# fs7_redraw.net
KiCad netlist of a schematic drawn in EAGLE
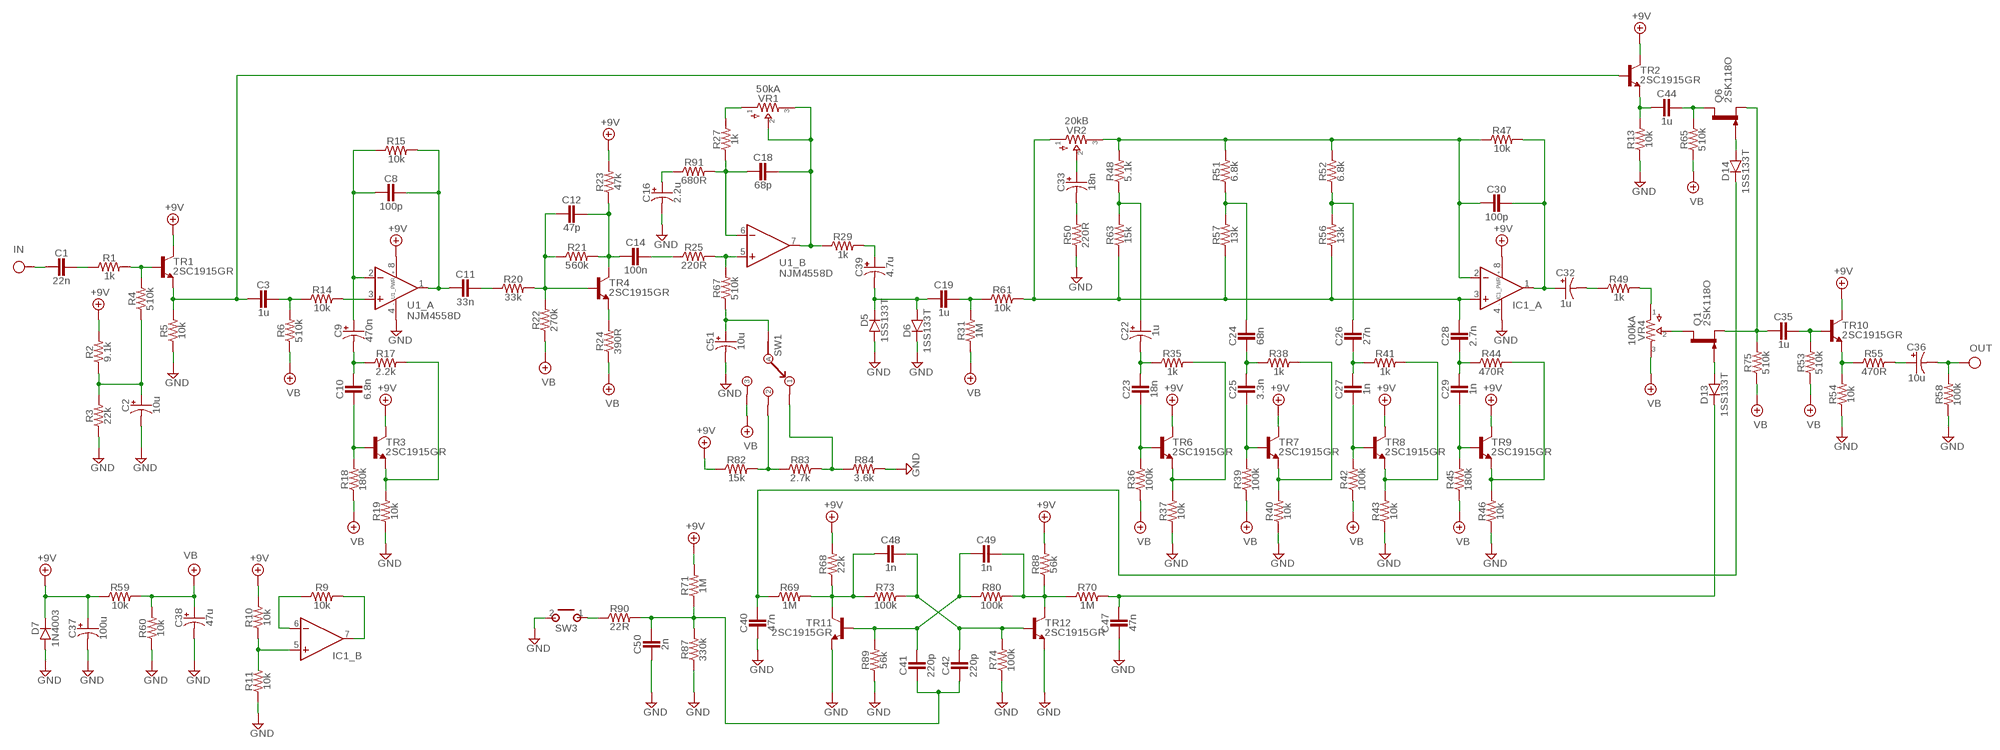
[diagram p0: schematic, sheet 1]

(export (version "E")
  (design (tool "Eeschema 10.0.6"))
  (components
    (comp (ref "C1")
      (value "22n")
      (footprint "eagle-import:BOX_SMALL")
      (libsource (lib "eagle-import") (part "CER/FILMBOX.1"))
    )
    (comp (ref "C2")
      (value "10u")
      (footprint "eagle-import:040_020")
      (libsource (lib "eagle-import") (part "0400"))
    )
    (comp (ref "C3")
      (value "1u")
      (footprint "eagle-import:BOX_SMALL")
      (libsource (lib "eagle-import") (part "CER/FILMBOX.1"))
    )
    (comp (ref "C8")
      (value "100p")
      (footprint "eagle-import:BOX_SMALL")
      (libsource (lib "eagle-import") (part "CER/FILMBOX.1"))
    )
    (comp (ref "C9")
      (value "470n")
      (footprint "eagle-import:040_020")
      (libsource (lib "eagle-import") (part "0400"))
    )
    (comp (ref "C10")
      (value "6.8n")
      (footprint "eagle-import:BOX_SMALL")
      (libsource (lib "eagle-import") (part "CER/FILMBOX.1"))
    )
    (comp (ref "C11")
      (value "33n")
      (footprint "eagle-import:BOX_SMALL")
      (libsource (lib "eagle-import") (part "CER/FILMBOX.1"))
    )
    (comp (ref "C12")
      (value "47p")
      (footprint "eagle-import:BOX_SMALL")
      (libsource (lib "eagle-import") (part "CER/FILMBOX.1"))
    )
    (comp (ref "C14")
      (value "100n")
      (footprint "eagle-import:BOX_SMALL")
      (libsource (lib "eagle-import") (part "CER/FILMBOX.1"))
    )
    (comp (ref "C16")
      (value "2.2u")
      (footprint "eagle-import:040_020")
      (libsource (lib "eagle-import") (part "0400"))
    )
    (comp (ref "C18")
      (value "68p")
      (footprint "eagle-import:BOX_SMALL")
      (libsource (lib "eagle-import") (part "CER/FILMBOX.1"))
    )
    (comp (ref "C19")
      (value "1u")
      (footprint "eagle-import:BOX_SMALL")
      (libsource (lib "eagle-import") (part "CER/FILMBOX.1"))
    )
    (comp (ref "C22")
      (value "1u")
      (footprint "eagle-import:040_020")
      (libsource (lib "eagle-import") (part "0400"))
    )
    (comp (ref "C23")
      (value "18n")
      (footprint "eagle-import:BOX_SMALL")
      (libsource (lib "eagle-import") (part "CER/FILMBOX.1"))
    )
    (comp (ref "C24")
      (value "68n")
      (footprint "eagle-import:BOX_SMALL")
      (libsource (lib "eagle-import") (part "CER/FILMBOX.1"))
    )
    (comp (ref "C25")
      (value "3.3n")
      (footprint "eagle-import:BOX_SMALL")
      (libsource (lib "eagle-import") (part "CER/FILMBOX.1"))
    )
    (comp (ref "C26")
      (value "27n")
      (footprint "eagle-import:BOX_SMALL")
      (libsource (lib "eagle-import") (part "CER/FILMBOX.1"))
    )
    (comp (ref "C27")
      (value "1n")
      (footprint "eagle-import:BOX_SMALL")
      (libsource (lib "eagle-import") (part "CER/FILMBOX.1"))
    )
    (comp (ref "C28")
      (value "2.7n")
      (footprint "eagle-import:BOX_SMALL")
      (libsource (lib "eagle-import") (part "CER/FILMBOX.1"))
    )
    (comp (ref "C29")
      (value "1n")
      (footprint "eagle-import:BOX_SMALL")
      (libsource (lib "eagle-import") (part "CER/FILMBOX.1"))
    )
    (comp (ref "C30")
      (value "100p")
      (footprint "eagle-import:BOX_SMALL")
      (libsource (lib "eagle-import") (part "CER/FILMBOX.1"))
    )
    (comp (ref "C32")
      (value "1u")
      (footprint "eagle-import:040_020")
      (libsource (lib "eagle-import") (part "0400"))
    )
    (comp (ref "C33")
      (value "18n")
      (footprint "eagle-import:040_020")
      (libsource (lib "eagle-import") (part "0400"))
    )
    (comp (ref "C35")
      (value "1u")
      (footprint "eagle-import:BOX_SMALL")
      (libsource (lib "eagle-import") (part "CER/FILMBOX.1"))
    )
    (comp (ref "C36")
      (value "10u")
      (footprint "eagle-import:040_020")
      (libsource (lib "eagle-import") (part "0400"))
    )
    (comp (ref "C37")
      (value "100u")
      (footprint "eagle-import:040_020")
      (libsource (lib "eagle-import") (part "0400"))
    )
    (comp (ref "C38")
      (value "47u")
      (footprint "eagle-import:040_020")
      (libsource (lib "eagle-import") (part "0400"))
    )
    (comp (ref "C39")
      (value "4.7u")
      (footprint "eagle-import:040_020")
      (libsource (lib "eagle-import") (part "0400"))
    )
    (comp (ref "C40")
      (value "47n")
      (footprint "eagle-import:BOX_SMALL")
      (libsource (lib "eagle-import") (part "CER/FILMBOX.1"))
    )
    (comp (ref "C41")
      (value "220p")
      (footprint "eagle-import:BOX_SMALL")
      (libsource (lib "eagle-import") (part "CER/FILMBOX.1"))
    )
    (comp (ref "C42")
      (value "220p")
      (footprint "eagle-import:BOX_SMALL")
      (libsource (lib "eagle-import") (part "CER/FILMBOX.1"))
    )
    (comp (ref "C44")
      (value "1u")
      (footprint "eagle-import:BOX_SMALL")
      (libsource (lib "eagle-import") (part "CER/FILMBOX.1"))
    )
    (comp (ref "C47")
      (value "47n")
      (footprint "eagle-import:BOX_SMALL")
      (libsource (lib "eagle-import") (part "CER/FILMBOX.1"))
    )
    (comp (ref "C48")
      (value "1n")
      (footprint "eagle-import:BOX_SMALL")
      (libsource (lib "eagle-import") (part "CER/FILMBOX.1"))
    )
    (comp (ref "C49")
      (value "1n")
      (footprint "eagle-import:BOX_SMALL")
      (libsource (lib "eagle-import") (part "CER/FILMBOX.1"))
    )
    (comp (ref "C50")
      (value "2n")
      (footprint "eagle-import:BOX_SMALL")
      (libsource (lib "eagle-import") (part "CER/FILMBOX.1"))
    )
    (comp (ref "C51")
      (value "10u")
      (footprint "eagle-import:040_020")
      (libsource (lib "eagle-import") (part "0400"))
    )
    (comp (ref "D5")
      (value "1SS133T")
      (footprint "eagle-import:DO41-2")
      (libsource (lib "eagle-import") (part "DO41.2"))
    )
    (comp (ref "D6")
      (value "1SS133T")
      (footprint "eagle-import:DO41-2")
      (libsource (lib "eagle-import") (part "DO41.2"))
    )
    (comp (ref "D7")
      (value "1N4003")
      (footprint "eagle-import:DO41-2")
      (libsource (lib "eagle-import") (part "DO41.2"))
    )
    (comp (ref "D13")
      (value "1SS133T")
      (footprint "eagle-import:DO41-2")
      (libsource (lib "eagle-import") (part "DO41.2"))
    )
    (comp (ref "D14")
      (value "1SS133T")
      (footprint "eagle-import:DO41-2")
      (libsource (lib "eagle-import") (part "DO41.2"))
    )
    (comp (ref "IC1")
      (value "DUALTH")
      (footprint "eagle-import:DIL0")
      (libsource (lib "eagle-import") (part "DUALTH"))
    )
    (comp (ref "Q1")
      (value "2SK118O")
      (footprint "eagle-import:TO92-")
      (libsource (lib "eagle-import") (part "2N5457"))
    )
    (comp (ref "Q6")
      (value "2SK118O")
      (footprint "eagle-import:TO92-")
      (libsource (lib "eagle-import") (part "2N5457"))
    )
    (comp (ref "R1")
      (value "1k")
      (footprint "eagle-import:R0207_3")
      (libsource (lib "eagle-import") (part "R_.3B"))
    )
    (comp (ref "R2")
      (value "9.1k")
      (footprint "eagle-import:R0207_3")
      (libsource (lib "eagle-import") (part "R_.3B"))
    )
    (comp (ref "R3")
      (value "22k")
      (footprint "eagle-import:R0207_3")
      (libsource (lib "eagle-import") (part "R_.3B"))
    )
    (comp (ref "R4")
      (value "510k")
      (footprint "eagle-import:R0207_3")
      (libsource (lib "eagle-import") (part "R_.3B"))
    )
    (comp (ref "R5")
      (value "10k")
      (footprint "eagle-import:R0207_3")
      (libsource (lib "eagle-import") (part "R_.3B"))
    )
    (comp (ref "R6")
      (value "510k")
      (footprint "eagle-import:R0207_3")
      (libsource (lib "eagle-import") (part "R_.3B"))
    )
    (comp (ref "R9")
      (value "10k")
      (footprint "eagle-import:R0207_3")
      (libsource (lib "eagle-import") (part "R_.3B"))
    )
    (comp (ref "R10")
      (value "10k")
      (footprint "eagle-import:R0207_3")
      (libsource (lib "eagle-import") (part "R_.3B"))
    )
    (comp (ref "R11")
      (value "10k")
      (footprint "eagle-import:R0207_3")
      (libsource (lib "eagle-import") (part "R_.3B"))
    )
    (comp (ref "R13")
      (value "10k")
      (footprint "eagle-import:R0207_3")
      (libsource (lib "eagle-import") (part "R_.3B"))
    )
    (comp (ref "R14")
      (value "10k")
      (footprint "eagle-import:R0207_3")
      (libsource (lib "eagle-import") (part "R_.3B"))
    )
    (comp (ref "R15")
      (value "10k")
      (footprint "eagle-import:R0207_3")
      (libsource (lib "eagle-import") (part "R_.3B"))
    )
    (comp (ref "R17")
      (value "2.2k")
      (footprint "eagle-import:R0207_3")
      (libsource (lib "eagle-import") (part "R_.3B"))
    )
    (comp (ref "R18")
      (value "180k")
      (footprint "eagle-import:R0207_3")
      (libsource (lib "eagle-import") (part "R_.3B"))
    )
    (comp (ref "R19")
      (value "10k")
      (footprint "eagle-import:R0207_3")
      (libsource (lib "eagle-import") (part "R_.3B"))
    )
    (comp (ref "R20")
      (value "33k")
      (footprint "eagle-import:R0207_3")
      (libsource (lib "eagle-import") (part "R_.3B"))
    )
    (comp (ref "R21")
      (value "560k")
      (footprint "eagle-import:R0207_3")
      (libsource (lib "eagle-import") (part "R_.3B"))
    )
    (comp (ref "R22")
      (value "270k")
      (footprint "eagle-import:R0207_3")
      (libsource (lib "eagle-import") (part "R_.3B"))
    )
    (comp (ref "R23")
      (value "47k")
      (footprint "eagle-import:R0207_3")
      (libsource (lib "eagle-import") (part "R_.3B"))
    )
    (comp (ref "R24")
      (value "390R")
      (footprint "eagle-import:R0207_3")
      (libsource (lib "eagle-import") (part "R_.3B"))
    )
    (comp (ref "R25")
      (value "220R")
      (footprint "eagle-import:R0207_3")
      (libsource (lib "eagle-import") (part "R_.3B"))
    )
    (comp (ref "R27")
      (value "1k")
      (footprint "eagle-import:R0207_3")
      (libsource (lib "eagle-import") (part "R_.3B"))
    )
    (comp (ref "R29")
      (value "1k")
      (footprint "eagle-import:R0207_3")
      (libsource (lib "eagle-import") (part "R_.3B"))
    )
    (comp (ref "R31")
      (value "1M")
      (footprint "eagle-import:R0207_3")
      (libsource (lib "eagle-import") (part "R_.3B"))
    )
    (comp (ref "R35")
      (value "1k")
      (footprint "eagle-import:R0207_3")
      (libsource (lib "eagle-import") (part "R_.3B"))
    )
    (comp (ref "R36")
      (value "100k")
      (footprint "eagle-import:R0207_3")
      (libsource (lib "eagle-import") (part "R_.3B"))
    )
    (comp (ref "R37")
      (value "10k")
      (footprint "eagle-import:R0207_3")
      (libsource (lib "eagle-import") (part "R_.3B"))
    )
    (comp (ref "R38")
      (value "1k")
      (footprint "eagle-import:R0207_3")
      (libsource (lib "eagle-import") (part "R_.3B"))
    )
    (comp (ref "R39")
      (value "100k")
      (footprint "eagle-import:R0207_3")
      (libsource (lib "eagle-import") (part "R_.3B"))
    )
    (comp (ref "R40")
      (value "10k")
      (footprint "eagle-import:R0207_3")
      (libsource (lib "eagle-import") (part "R_.3B"))
    )
    (comp (ref "R41")
      (value "1k")
      (footprint "eagle-import:R0207_3")
      (libsource (lib "eagle-import") (part "R_.3B"))
    )
    (comp (ref "R42")
      (value "100k")
      (footprint "eagle-import:R0207_3")
      (libsource (lib "eagle-import") (part "R_.3B"))
    )
    (comp (ref "R43")
      (value "10k")
      (footprint "eagle-import:R0207_3")
      (libsource (lib "eagle-import") (part "R_.3B"))
    )
    (comp (ref "R44")
      (value "470R")
      (footprint "eagle-import:R0207_3")
      (libsource (lib "eagle-import") (part "R_.3B"))
    )
    (comp (ref "R45")
      (value "180k")
      (footprint "eagle-import:R0207_3")
      (libsource (lib "eagle-import") (part "R_.3B"))
    )
    (comp (ref "R46")
      (value "10k")
      (footprint "eagle-import:R0207_3")
      (libsource (lib "eagle-import") (part "R_.3B"))
    )
    (comp (ref "R47")
      (value "10k")
      (footprint "eagle-import:R0207_3")
      (libsource (lib "eagle-import") (part "R_.3B"))
    )
    (comp (ref "R48")
      (value "5.1k")
      (footprint "eagle-import:R0207_3")
      (libsource (lib "eagle-import") (part "R_.3B"))
    )
    (comp (ref "R49")
      (value "1k")
      (footprint "eagle-import:R0207_3")
      (libsource (lib "eagle-import") (part "R_.3B"))
    )
    (comp (ref "R50")
      (value "220R")
      (footprint "eagle-import:R0207_3")
      (libsource (lib "eagle-import") (part "R_.3B"))
    )
    (comp (ref "R51")
      (value "6.8k")
      (footprint "eagle-import:R0207_3")
      (libsource (lib "eagle-import") (part "R_.3B"))
    )
    (comp (ref "R52")
      (value "6.8k")
      (footprint "eagle-import:R0207_3")
      (libsource (lib "eagle-import") (part "R_.3B"))
    )
    (comp (ref "R53")
      (value "510k")
      (footprint "eagle-import:R0207_3")
      (libsource (lib "eagle-import") (part "R_.3B"))
    )
    (comp (ref "R54")
      (value "10k")
      (footprint "eagle-import:R0207_3")
      (libsource (lib "eagle-import") (part "R_.3B"))
    )
    (comp (ref "R55")
      (value "470R")
      (footprint "eagle-import:R0207_3")
      (libsource (lib "eagle-import") (part "R_.3B"))
    )
    (comp (ref "R56")
      (value "13k")
      (footprint "eagle-import:R0207_3")
      (libsource (lib "eagle-import") (part "R_.3B"))
    )
    (comp (ref "R57")
      (value "13k")
      (footprint "eagle-import:R0207_3")
      (libsource (lib "eagle-import") (part "R_.3B"))
    )
    (comp (ref "R58")
      (value "100k")
      (footprint "eagle-import:R0207_3")
      (libsource (lib "eagle-import") (part "R_.3B"))
    )
    (comp (ref "R59")
      (value "10k")
      (footprint "eagle-import:R0207_3")
      (libsource (lib "eagle-import") (part "R_.3B"))
    )
    (comp (ref "R60")
      (value "10k")
      (footprint "eagle-import:R0207_3")
      (libsource (lib "eagle-import") (part "R_.3B"))
    )
    (comp (ref "R61")
      (value "10k")
      (footprint "eagle-import:R0207_3")
      (libsource (lib "eagle-import") (part "R_.3B"))
    )
    (comp (ref "R63")
      (value "15k")
      (footprint "eagle-import:R0207_3")
      (libsource (lib "eagle-import") (part "R_.3B"))
    )
    (comp (ref "R65")
      (value "510k")
      (footprint "eagle-import:R0207_3")
      (libsource (lib "eagle-import") (part "R_.3B"))
    )
    (comp (ref "R67")
      (value "510k")
      (footprint "eagle-import:R0207_3")
      (libsource (lib "eagle-import") (part "R_.3B"))
    )
    (comp (ref "R68")
      (value "22k")
      (footprint "eagle-import:R0207_3")
      (libsource (lib "eagle-import") (part "R_.3B"))
    )
    (comp (ref "R69")
      (value "1M")
      (footprint "eagle-import:R0207_3")
      (libsource (lib "eagle-import") (part "R_.3B"))
    )
    (comp (ref "R70")
      (value "1M")
      (footprint "eagle-import:R0207_3")
      (libsource (lib "eagle-import") (part "R_.3B"))
    )
    (comp (ref "R71")
      (value "1M")
      (footprint "eagle-import:R0207_3")
      (libsource (lib "eagle-import") (part "R_.3B"))
    )
    (comp (ref "R73")
      (value "100k")
      (footprint "eagle-import:R0207_3")
      (libsource (lib "eagle-import") (part "R_.3B"))
    )
    (comp (ref "R74")
      (value "100k")
      (footprint "eagle-import:R0207_3")
      (libsource (lib "eagle-import") (part "R_.3B"))
    )
    (comp (ref "R75")
      (value "510k")
      (footprint "eagle-import:R0207_3")
      (libsource (lib "eagle-import") (part "R_.3B"))
    )
    (comp (ref "R80")
      (value "100k")
      (footprint "eagle-import:R0207_3")
      (libsource (lib "eagle-import") (part "R_.3B"))
    )
    (comp (ref "R82")
      (value "15k")
      (footprint "eagle-import:R0207_3")
      (libsource (lib "eagle-import") (part "R_.3B"))
    )
    (comp (ref "R83")
      (value "2.7k")
      (footprint "eagle-import:R0207_3")
      (libsource (lib "eagle-import") (part "R_.3B"))
    )
    (comp (ref "R84")
      (value "3.6k")
      (footprint "eagle-import:R0207_3")
      (libsource (lib "eagle-import") (part "R_.3B"))
    )
    (comp (ref "R87")
      (value "330k")
      (footprint "eagle-import:R0207_3")
      (libsource (lib "eagle-import") (part "R_.3B"))
    )
    (comp (ref "R88")
      (value "56k")
      (footprint "eagle-import:R0207_3")
      (libsource (lib "eagle-import") (part "R_.3B"))
    )
    (comp (ref "R89")
      (value "56k")
      (footprint "eagle-import:R0207_3")
      (libsource (lib "eagle-import") (part "R_.3B"))
    )
    (comp (ref "R90")
      (value "22R")
      (footprint "eagle-import:R0207_3")
      (libsource (lib "eagle-import") (part "R_.3B"))
    )
    (comp (ref "R91")
      (value "680R")
      (footprint "eagle-import:R0207_3")
      (libsource (lib "eagle-import") (part "R_.3B"))
    )
    (comp (ref "SW1")
      (value "1P3T")
      (footprint "eagle-import:1P3T")
      (libsource (lib "eagle-import") (part "1P3T"))
    )
    (comp (ref "SW3")
      (value "MOMENTARY")
      (footprint "eagle-import:SPST")
      (libsource (lib "eagle-import") (part "MOMENTARY"))
    )
    (comp (ref "TR1")
      (value "2SC1915GR")
      (footprint "eagle-import:TO92-")
      (libsource (lib "eagle-import") (part "2SC828A"))
    )
    (comp (ref "TR2")
      (value "2SC1915GR")
      (footprint "eagle-import:TO92-")
      (libsource (lib "eagle-import") (part "2SC828A"))
    )
    (comp (ref "TR3")
      (value "2SC1915GR")
      (footprint "eagle-import:TO92-")
      (libsource (lib "eagle-import") (part "2SC828A"))
    )
    (comp (ref "TR4")
      (value "2SC1915GR")
      (footprint "eagle-import:TO92-")
      (libsource (lib "eagle-import") (part "2SC828A"))
    )
    (comp (ref "TR6")
      (value "2SC1915GR")
      (footprint "eagle-import:TO92-")
      (libsource (lib "eagle-import") (part "2SC828A"))
    )
    (comp (ref "TR7")
      (value "2SC1915GR")
      (footprint "eagle-import:TO92-")
      (libsource (lib "eagle-import") (part "2SC828A"))
    )
    (comp (ref "TR8")
      (value "2SC1915GR")
      (footprint "eagle-import:TO92-")
      (libsource (lib "eagle-import") (part "2SC828A"))
    )
    (comp (ref "TR9")
      (value "2SC1915GR")
      (footprint "eagle-import:TO92-")
      (libsource (lib "eagle-import") (part "2SC828A"))
    )
    (comp (ref "TR10")
      (value "2SC1915GR")
      (footprint "eagle-import:TO92-")
      (libsource (lib "eagle-import") (part "2SC828A"))
    )
    (comp (ref "TR11")
      (value "2SC1915GR")
      (footprint "eagle-import:TO92-")
      (libsource (lib "eagle-import") (part "2SC828A"))
    )
    (comp (ref "TR12")
      (value "2SC1915GR")
      (footprint "eagle-import:TO92-")
      (libsource (lib "eagle-import") (part "2SC828A"))
    )
    (comp (ref "U1")
      (value "NJM4558D")
      (footprint "eagle-import:DIL0")
      (libsource (lib "eagle-import") (part "DUALTH"))
    )
    (comp (ref "VR1")
      (value "50kA")
      (footprint "eagle-import:16MM")
      (libsource (lib "eagle-import") (part "POTS16MM"))
    )
    (comp (ref "VR2")
      (value "20kB")
      (footprint "eagle-import:16MM")
      (libsource (lib "eagle-import") (part "POTS16MM"))
    )
    (comp (ref "VR4")
      (value "100kA")
      (footprint "eagle-import:16MM")
      (libsource (lib "eagle-import") (part "POTS16MM"))
    )
  )
  (nets
    (net (code "1") (name "+9V") (class "Default")
      (node (ref "C37") (pin "+") (pinfunction "+_+") (pintype "passive"))
      (node (ref "D7") (pin "C") (pinfunction "C_C") (pintype "passive"))
      (node (ref "IC1") (pin "8") (pinfunction "V+_8") (pintype "power_in"))
      (node (ref "R10") (pin "2") (pinfunction "2_2") (pintype "passive"))
      (node (ref "R2") (pin "2") (pinfunction "2_2") (pintype "passive"))
      (node (ref "R23") (pin "2") (pinfunction "2_2") (pintype "passive"))
      (node (ref "R59") (pin "1") (pinfunction "1_1") (pintype "passive"))
      (node (ref "R68") (pin "2") (pinfunction "2_2") (pintype "passive"))
      (node (ref "R71") (pin "2") (pinfunction "2_2") (pintype "passive"))
      (node (ref "R82") (pin "1") (pinfunction "1_1") (pintype "passive"))
      (node (ref "R88") (pin "2") (pinfunction "2_2") (pintype "passive"))
      (node (ref "TR1") (pin "2") (pinfunction "C_2") (pintype "passive"))
      (node (ref "TR10") (pin "2") (pinfunction "C_2") (pintype "passive"))
      (node (ref "TR2") (pin "2") (pinfunction "C_2") (pintype "passive"))
      (node (ref "TR3") (pin "2") (pinfunction "C_2") (pintype "passive"))
      (node (ref "TR6") (pin "2") (pinfunction "C_2") (pintype "passive"))
      (node (ref "TR7") (pin "2") (pinfunction "C_2") (pintype "passive"))
      (node (ref "TR8") (pin "2") (pinfunction "C_2") (pintype "passive"))
      (node (ref "TR9") (pin "2") (pinfunction "C_2") (pintype "passive"))
      (node (ref "U1") (pin "8") (pinfunction "V+_8") (pintype "power_in"))
    )
    (net (code "2") (name "GND") (class "Default")
      (node (ref "C16") (pin "-") (pinfunction "-_-") (pintype "passive"))
      (node (ref "C2") (pin "-") (pinfunction "-_-") (pintype "passive"))
      (node (ref "C37") (pin "-") (pinfunction "-_-") (pintype "passive"))
      (node (ref "C38") (pin "-") (pinfunction "-_-") (pintype "passive"))
      (node (ref "C40") (pin "2") (pinfunction "2_2") (pintype "passive"))
      (node (ref "C47") (pin "2") (pinfunction "2_2") (pintype "passive"))
      (node (ref "C50") (pin "2") (pinfunction "2_2") (pintype "passive"))
      (node (ref "C51") (pin "-") (pinfunction "-_-") (pintype "passive"))
      (node (ref "D5") (pin "A") (pinfunction "A_A") (pintype "passive"))
      (node (ref "D6") (pin "C") (pinfunction "C_C") (pintype "passive"))
      (node (ref "D7") (pin "A") (pinfunction "A_A") (pintype "passive"))
      (node (ref "IC1") (pin "4") (pinfunction "V-_4") (pintype "power_in"))
      (node (ref "R11") (pin "1") (pinfunction "1_1") (pintype "passive"))
      (node (ref "R13") (pin "1") (pinfunction "1_1") (pintype "passive"))
      (node (ref "R19") (pin "1") (pinfunction "1_1") (pintype "passive"))
      (node (ref "R3") (pin "1") (pinfunction "1_1") (pintype "passive"))
      (node (ref "R37") (pin "1") (pinfunction "1_1") (pintype "passive"))
      (node (ref "R40") (pin "1") (pinfunction "1_1") (pintype "passive"))
      (node (ref "R43") (pin "1") (pinfunction "1_1") (pintype "passive"))
      (node (ref "R46") (pin "1") (pinfunction "1_1") (pintype "passive"))
      (node (ref "R5") (pin "1") (pinfunction "1_1") (pintype "passive"))
      (node (ref "R50") (pin "1") (pinfunction "1_1") (pintype "passive"))
      (node (ref "R54") (pin "1") (pinfunction "1_1") (pintype "passive"))
      (node (ref "R58") (pin "1") (pinfunction "1_1") (pintype "passive"))
      (node (ref "R60") (pin "1") (pinfunction "1_1") (pintype "passive"))
      (node (ref "R74") (pin "1") (pinfunction "1_1") (pintype "passive"))
      (node (ref "R84") (pin "2") (pinfunction "2_2") (pintype "passive"))
      (node (ref "R87") (pin "1") (pinfunction "1_1") (pintype "passive"))
      (node (ref "R89") (pin "1") (pinfunction "1_1") (pintype "passive"))
      (node (ref "SW3") (pin "2") (pinfunction "S_2") (pintype "passive"))
      (node (ref "TR11") (pin "3") (pinfunction "E_3") (pintype "passive"))
      (node (ref "TR12") (pin "3") (pinfunction "E_3") (pintype "passive"))
      (node (ref "U1") (pin "4") (pinfunction "V-_4") (pintype "power_in"))
    )
    (net (code "3") (name "IN") (class "Default")
      (node (ref "C1") (pin "2") (pinfunction "2_2") (pintype "passive"))
    )
    (net (code "4") (name "Net-(C1-Pad1)") (class "Default")
      (node (ref "C1") (pin "1") (pinfunction "1_1") (pintype "passive"))
      (node (ref "R1") (pin "1") (pinfunction "1_1") (pintype "passive"))
    )
    (net (code "5") (name "Net-(C2-Pad+)") (class "Default")
      (node (ref "C2") (pin "+") (pinfunction "+_+") (pintype "passive"))
      (node (ref "R2") (pin "1") (pinfunction "1_1") (pintype "passive"))
      (node (ref "R3") (pin "2") (pinfunction "2_2") (pintype "passive"))
      (node (ref "R4") (pin "1") (pinfunction "1_1") (pintype "passive"))
    )
    (net (code "6") (name "Net-(C3-Pad1)") (class "Default")
      (node (ref "C3") (pin "1") (pinfunction "1_1") (pintype "passive"))
      (node (ref "R14") (pin "1") (pinfunction "1_1") (pintype "passive"))
      (node (ref "R6") (pin "2") (pinfunction "2_2") (pintype "passive"))
    )
    (net (code "7") (name "Net-(C10-Pad1)") (class "Default")
      (node (ref "C10") (pin "1") (pinfunction "1_1") (pintype "passive"))
      (node (ref "C9") (pin "-") (pinfunction "-_-") (pintype "passive"))
      (node (ref "R17") (pin "1") (pinfunction "1_1") (pintype "passive"))
    )
    (net (code "8") (name "Net-(C11-Pad1)") (class "Default")
      (node (ref "C11") (pin "1") (pinfunction "1_1") (pintype "passive"))
      (node (ref "R20") (pin "1") (pinfunction "1_1") (pintype "passive"))
    )
    (net (code "9") (name "Net-(C14-Pad1)") (class "Default")
      (node (ref "C14") (pin "1") (pinfunction "1_1") (pintype "passive"))
      (node (ref "R25") (pin "1") (pinfunction "1_1") (pintype "passive"))
    )
    (net (code "10") (name "Net-(C16-Pad+)") (class "Default")
      (node (ref "C16") (pin "+") (pinfunction "+_+") (pintype "passive"))
      (node (ref "R91") (pin "1") (pinfunction "1_1") (pintype "passive"))
    )
    (net (code "11") (name "Net-(C19-Pad1)") (class "Default")
      (node (ref "C19") (pin "1") (pinfunction "1_1") (pintype "passive"))
      (node (ref "R31") (pin "2") (pinfunction "2_2") (pintype "passive"))
      (node (ref "R61") (pin "1") (pinfunction "1_1") (pintype "passive"))
    )
    (net (code "12") (name "Net-(C19-Pad2)") (class "Default")
      (node (ref "C19") (pin "2") (pinfunction "2_2") (pintype "passive"))
      (node (ref "C39") (pin "-") (pinfunction "-_-") (pintype "passive"))
      (node (ref "D5") (pin "C") (pinfunction "C_C") (pintype "passive"))
      (node (ref "D6") (pin "A") (pinfunction "A_A") (pintype "passive"))
    )
    (net (code "13") (name "Net-(C22-Pad+)") (class "Default")
      (node (ref "C22") (pin "+") (pinfunction "+_+") (pintype "passive"))
      (node (ref "R48") (pin "1") (pinfunction "1_1") (pintype "passive"))
      (node (ref "R63") (pin "2") (pinfunction "2_2") (pintype "passive"))
    )
    (net (code "14") (name "Net-(C22-Pad-)") (class "Default")
      (node (ref "C22") (pin "-") (pinfunction "-_-") (pintype "passive"))
      (node (ref "C23") (pin "1") (pinfunction "1_1") (pintype "passive"))
      (node (ref "R35") (pin "1") (pinfunction "1_1") (pintype "passive"))
    )
    (net (code "15") (name "Net-(C24-Pad1)") (class "Default")
      (node (ref "C24") (pin "1") (pinfunction "1_1") (pintype "passive"))
      (node (ref "R51") (pin "1") (pinfunction "1_1") (pintype "passive"))
      (node (ref "R57") (pin "2") (pinfunction "2_2") (pintype "passive"))
    )
    (net (code "16") (name "Net-(C24-Pad2)") (class "Default")
      (node (ref "C24") (pin "2") (pinfunction "2_2") (pintype "passive"))
      (node (ref "C25") (pin "1") (pinfunction "1_1") (pintype "passive"))
      (node (ref "R38") (pin "1") (pinfunction "1_1") (pintype "passive"))
    )
    (net (code "17") (name "Net-(C26-Pad1)") (class "Default")
      (node (ref "C26") (pin "1") (pinfunction "1_1") (pintype "passive"))
      (node (ref "R52") (pin "1") (pinfunction "1_1") (pintype "passive"))
      (node (ref "R56") (pin "2") (pinfunction "2_2") (pintype "passive"))
    )
    (net (code "18") (name "Net-(C26-Pad2)") (class "Default")
      (node (ref "C26") (pin "2") (pinfunction "2_2") (pintype "passive"))
      (node (ref "C27") (pin "1") (pinfunction "1_1") (pintype "passive"))
      (node (ref "R41") (pin "1") (pinfunction "1_1") (pintype "passive"))
    )
    (net (code "19") (name "Net-(C28-Pad2)") (class "Default")
      (node (ref "C28") (pin "2") (pinfunction "2_2") (pintype "passive"))
      (node (ref "C29") (pin "1") (pinfunction "1_1") (pintype "passive"))
      (node (ref "R44") (pin "1") (pinfunction "1_1") (pintype "passive"))
    )
    (net (code "20") (name "Net-(C32-Pad-)") (class "Default")
      (node (ref "C32") (pin "-") (pinfunction "-_-") (pintype "passive"))
      (node (ref "R49") (pin "1") (pinfunction "1_1") (pintype "passive"))
    )
    (net (code "21") (name "Net-(C33-Pad+)") (class "Default")
      (node (ref "C33") (pin "+") (pinfunction "+_+") (pintype "passive"))
      (node (ref "VR2") (pin "2") (pinfunction "2_2") (pintype "passive"))
    )
    (net (code "22") (name "Net-(C33-Pad-)") (class "Default")
      (node (ref "C33") (pin "-") (pinfunction "-_-") (pintype "passive"))
      (node (ref "R50") (pin "2") (pinfunction "2_2") (pintype "passive"))
    )
    (net (code "23") (name "Net-(C36-Pad+)") (class "Default")
      (node (ref "C36") (pin "+") (pinfunction "+_+") (pintype "passive"))
      (node (ref "R55") (pin "2") (pinfunction "2_2") (pintype "passive"))
    )
    (net (code "24") (name "Net-(C39-Pad+)") (class "Default")
      (node (ref "C39") (pin "+") (pinfunction "+_+") (pintype "passive"))
      (node (ref "R29") (pin "2") (pinfunction "2_2") (pintype "passive"))
    )
    (net (code "25") (name "Net-(C40-Pad1)") (class "Default")
      (node (ref "C40") (pin "1") (pinfunction "1_1") (pintype "passive"))
      (node (ref "D14") (pin "C") (pinfunction "C_C") (pintype "passive"))
      (node (ref "R69") (pin "1") (pinfunction "1_1") (pintype "passive"))
    )
    (net (code "26") (name "Net-(C41-Pad2)") (class "Default")
      (node (ref "C41") (pin "2") (pinfunction "2_2") (pintype "passive"))
      (node (ref "C42") (pin "2") (pinfunction "2_2") (pintype "passive"))
      (node (ref "C50") (pin "1") (pinfunction "1_1") (pintype "passive"))
      (node (ref "R71") (pin "1") (pinfunction "1_1") (pintype "passive"))
      (node (ref "R87") (pin "2") (pinfunction "2_2") (pintype "passive"))
      (node (ref "R90") (pin "2") (pinfunction "2_2") (pintype "passive"))
    )
    (net (code "27") (name "Net-(C47-Pad1)") (class "Default")
      (node (ref "C47") (pin "1") (pinfunction "1_1") (pintype "passive"))
      (node (ref "D13") (pin "C") (pinfunction "C_C") (pintype "passive"))
      (node (ref "R70") (pin "2") (pinfunction "2_2") (pintype "passive"))
    )
    (net (code "28") (name "Net-(IC1A-+IN)") (class "Default")
      (node (ref "C28") (pin "1") (pinfunction "1_1") (pintype "passive"))
      (node (ref "IC1") (pin "3") (pinfunction "+IN_3") (pintype "input"))
      (node (ref "R56") (pin "1") (pinfunction "1_1") (pintype "passive"))
      (node (ref "R57") (pin "1") (pinfunction "1_1") (pintype "passive"))
      (node (ref "R61") (pin "2") (pinfunction "2_2") (pintype "passive"))
      (node (ref "R63") (pin "1") (pinfunction "1_1") (pintype "passive"))
      (node (ref "VR2") (pin "1") (pinfunction "1_1") (pintype "passive"))
    )
    (net (code "29") (name "Net-(IC1A--IN)") (class "Default")
      (node (ref "C30") (pin "2") (pinfunction "2_2") (pintype "passive"))
      (node (ref "IC1") (pin "2") (pinfunction "-IN_2") (pintype "input"))
      (node (ref "R47") (pin "1") (pinfunction "1_1") (pintype "passive"))
      (node (ref "R48") (pin "2") (pinfunction "2_2") (pintype "passive"))
      (node (ref "R51") (pin "2") (pinfunction "2_2") (pintype "passive"))
      (node (ref "R52") (pin "2") (pinfunction "2_2") (pintype "passive"))
      (node (ref "VR2") (pin "3") (pinfunction "3_3") (pintype "passive"))
    )
    (net (code "30") (name "Net-(IC1A-OUT)") (class "Default")
      (node (ref "C30") (pin "1") (pinfunction "1_1") (pintype "passive"))
      (node (ref "C32") (pin "+") (pinfunction "+_+") (pintype "passive"))
      (node (ref "IC1") (pin "1") (pinfunction "OUT_1") (pintype "output"))
      (node (ref "R47") (pin "2") (pinfunction "2_2") (pintype "passive"))
    )
    (net (code "31") (name "Net-(IC1B-+IN)") (class "Default")
      (node (ref "IC1") (pin "5") (pinfunction "+IN_5") (pintype "input"))
      (node (ref "R10") (pin "1") (pinfunction "1_1") (pintype "passive"))
    )
    (net (code "32") (name "Net-(IC1B--IN)") (class "Default")
      (node (ref "IC1") (pin "6") (pinfunction "-IN_6") (pintype "input"))
      (node (ref "R9") (pin "1") (pinfunction "1_1") (pintype "passive"))
    )
    (net (code "33") (name "Net-(IC1B-OUT)") (class "Default")
      (node (ref "IC1") (pin "7") (pinfunction "OUT_7") (pintype "output"))
      (node (ref "R9") (pin "2") (pinfunction "2_2") (pintype "passive"))
    )
    (net (code "34") (name "Net-(Q1-D)") (class "Default")
      (node (ref "Q1") (pin "3") (pinfunction "D_3") (pintype "passive"))
      (node (ref "VR4") (pin "2") (pinfunction "2_2") (pintype "passive"))
    )
    (net (code "35") (name "Net-(Q1-G)") (class "Default")
      (node (ref "D13") (pin "A") (pinfunction "A_A") (pintype "passive"))
      (node (ref "Q1") (pin "1") (pinfunction "G_1") (pintype "passive"))
    )
    (net (code "36") (name "Net-(Q1-S)") (class "Default")
      (node (ref "C35") (pin "2") (pinfunction "2_2") (pintype "passive"))
      (node (ref "Q1") (pin "2") (pinfunction "S_2") (pintype "passive"))
      (node (ref "Q6") (pin "2") (pinfunction "S_2") (pintype "passive"))
      (node (ref "R75") (pin "2") (pinfunction "2_2") (pintype "passive"))
    )
    (net (code "37") (name "Net-(Q6-D)") (class "Default")
      (node (ref "C44") (pin "1") (pinfunction "1_1") (pintype "passive"))
      (node (ref "Q6") (pin "3") (pinfunction "D_3") (pintype "passive"))
      (node (ref "R65") (pin "2") (pinfunction "2_2") (pintype "passive"))
    )
    (net (code "38") (name "Net-(Q6-G)") (class "Default")
      (node (ref "D14") (pin "A") (pinfunction "A_A") (pintype "passive"))
      (node (ref "Q6") (pin "1") (pinfunction "G_1") (pintype "passive"))
    )
    (net (code "39") (name "Net-(R27-Pad2)") (class "Default")
      (node (ref "R27") (pin "2") (pinfunction "2_2") (pintype "passive"))
      (node (ref "VR1") (pin "1") (pinfunction "1_1") (pintype "passive"))
    )
    (net (code "40") (name "Net-(R49-Pad2)") (class "Default")
      (node (ref "R49") (pin "2") (pinfunction "2_2") (pintype "passive"))
      (node (ref "VR4") (pin "1") (pinfunction "1_1") (pintype "passive"))
    )
    (net (code "41") (name "Net-(SW1-1)") (class "Default")
      (node (ref "R83") (pin "2") (pinfunction "2_2") (pintype "passive"))
      (node (ref "R84") (pin "1") (pinfunction "1_1") (pintype "passive"))
      (node (ref "SW1") (pin "P$2") (pinfunction "1_P$2") (pintype "bidirectional"))
    )
    (net (code "42") (name "Net-(SW1-2)") (class "Default")
      (node (ref "R82") (pin "2") (pinfunction "2_2") (pintype "passive"))
      (node (ref "R83") (pin "1") (pinfunction "1_1") (pintype "passive"))
      (node (ref "SW1") (pin "P$3") (pinfunction "2_P$3") (pintype "bidirectional"))
    )
    (net (code "43") (name "Net-(SW1-A)") (class "Default")
      (node (ref "C51") (pin "+") (pinfunction "+_+") (pintype "passive"))
      (node (ref "R67") (pin "1") (pinfunction "1_1") (pintype "passive"))
      (node (ref "SW1") (pin "P$1") (pinfunction "A_P$1") (pintype "bidirectional"))
    )
    (net (code "44") (name "Net-(SW3-P)") (class "Default")
      (node (ref "R90") (pin "1") (pinfunction "1_1") (pintype "passive"))
      (node (ref "SW3") (pin "1") (pinfunction "P_1") (pintype "passive"))
    )
    (net (code "45") (name "Net-(TR1-B)") (class "Default")
      (node (ref "R1") (pin "2") (pinfunction "2_2") (pintype "passive"))
      (node (ref "R4") (pin "2") (pinfunction "2_2") (pintype "passive"))
      (node (ref "TR1") (pin "1") (pinfunction "B_1") (pintype "passive"))
    )
    (net (code "46") (name "Net-(TR1-E)") (class "Default")
      (node (ref "C3") (pin "2") (pinfunction "2_2") (pintype "passive"))
      (node (ref "R5") (pin "2") (pinfunction "2_2") (pintype "passive"))
      (node (ref "TR1") (pin "3") (pinfunction "E_3") (pintype "passive"))
      (node (ref "TR2") (pin "1") (pinfunction "B_1") (pintype "passive"))
    )
    (net (code "47") (name "Net-(TR2-E)") (class "Default")
      (node (ref "C44") (pin "2") (pinfunction "2_2") (pintype "passive"))
      (node (ref "R13") (pin "2") (pinfunction "2_2") (pintype "passive"))
      (node (ref "TR2") (pin "3") (pinfunction "E_3") (pintype "passive"))
    )
    (net (code "48") (name "Net-(TR3-B)") (class "Default")
      (node (ref "C10") (pin "2") (pinfunction "2_2") (pintype "passive"))
      (node (ref "R18") (pin "2") (pinfunction "2_2") (pintype "passive"))
      (node (ref "TR3") (pin "1") (pinfunction "B_1") (pintype "passive"))
    )
    (net (code "49") (name "Net-(TR3-E)") (class "Default")
      (node (ref "R17") (pin "2") (pinfunction "2_2") (pintype "passive"))
      (node (ref "R19") (pin "2") (pinfunction "2_2") (pintype "passive"))
      (node (ref "TR3") (pin "3") (pinfunction "E_3") (pintype "passive"))
    )
    (net (code "50") (name "Net-(TR4-B)") (class "Default")
      (node (ref "C12") (pin "2") (pinfunction "2_2") (pintype "passive"))
      (node (ref "R20") (pin "2") (pinfunction "2_2") (pintype "passive"))
      (node (ref "R21") (pin "1") (pinfunction "1_1") (pintype "passive"))
      (node (ref "R22") (pin "2") (pinfunction "2_2") (pintype "passive"))
      (node (ref "TR4") (pin "1") (pinfunction "B_1") (pintype "passive"))
    )
    (net (code "51") (name "Net-(TR4-C)") (class "Default")
      (node (ref "C12") (pin "1") (pinfunction "1_1") (pintype "passive"))
      (node (ref "C14") (pin "2") (pinfunction "2_2") (pintype "passive"))
      (node (ref "R21") (pin "2") (pinfunction "2_2") (pintype "passive"))
      (node (ref "R23") (pin "1") (pinfunction "1_1") (pintype "passive"))
      (node (ref "TR4") (pin "2") (pinfunction "C_2") (pintype "passive"))
    )
    (net (code "52") (name "Net-(TR4-E)") (class "Default")
      (node (ref "R24") (pin "2") (pinfunction "2_2") (pintype "passive"))
      (node (ref "TR4") (pin "3") (pinfunction "E_3") (pintype "passive"))
    )
    (net (code "53") (name "Net-(TR6-B)") (class "Default")
      (node (ref "C23") (pin "2") (pinfunction "2_2") (pintype "passive"))
      (node (ref "R36") (pin "2") (pinfunction "2_2") (pintype "passive"))
      (node (ref "TR6") (pin "1") (pinfunction "B_1") (pintype "passive"))
    )
    (net (code "54") (name "Net-(TR6-E)") (class "Default")
      (node (ref "R35") (pin "2") (pinfunction "2_2") (pintype "passive"))
      (node (ref "R37") (pin "2") (pinfunction "2_2") (pintype "passive"))
      (node (ref "TR6") (pin "3") (pinfunction "E_3") (pintype "passive"))
    )
    (net (code "55") (name "Net-(TR7-B)") (class "Default")
      (node (ref "C25") (pin "2") (pinfunction "2_2") (pintype "passive"))
      (node (ref "R39") (pin "2") (pinfunction "2_2") (pintype "passive"))
      (node (ref "TR7") (pin "1") (pinfunction "B_1") (pintype "passive"))
    )
    (net (code "56") (name "Net-(TR7-E)") (class "Default")
      (node (ref "R38") (pin "2") (pinfunction "2_2") (pintype "passive"))
      (node (ref "R40") (pin "2") (pinfunction "2_2") (pintype "passive"))
      (node (ref "TR7") (pin "3") (pinfunction "E_3") (pintype "passive"))
    )
    (net (code "57") (name "Net-(TR8-B)") (class "Default")
      (node (ref "C27") (pin "2") (pinfunction "2_2") (pintype "passive"))
      (node (ref "R42") (pin "2") (pinfunction "2_2") (pintype "passive"))
      (node (ref "TR8") (pin "1") (pinfunction "B_1") (pintype "passive"))
    )
    (net (code "58") (name "Net-(TR8-E)") (class "Default")
      (node (ref "R41") (pin "2") (pinfunction "2_2") (pintype "passive"))
      (node (ref "R43") (pin "2") (pinfunction "2_2") (pintype "passive"))
      (node (ref "TR8") (pin "3") (pinfunction "E_3") (pintype "passive"))
    )
    (net (code "59") (name "Net-(TR9-B)") (class "Default")
      (node (ref "C29") (pin "2") (pinfunction "2_2") (pintype "passive"))
      (node (ref "R45") (pin "2") (pinfunction "2_2") (pintype "passive"))
      (node (ref "TR9") (pin "1") (pinfunction "B_1") (pintype "passive"))
    )
    (net (code "60") (name "Net-(TR9-E)") (class "Default")
      (node (ref "R44") (pin "2") (pinfunction "2_2") (pintype "passive"))
      (node (ref "R46") (pin "2") (pinfunction "2_2") (pintype "passive"))
      (node (ref "TR9") (pin "3") (pinfunction "E_3") (pintype "passive"))
    )
    (net (code "61") (name "Net-(TR10-B)") (class "Default")
      (node (ref "C35") (pin "1") (pinfunction "1_1") (pintype "passive"))
      (node (ref "R53") (pin "2") (pinfunction "2_2") (pintype "passive"))
      (node (ref "TR10") (pin "1") (pinfunction "B_1") (pintype "passive"))
    )
    (net (code "62") (name "Net-(TR10-E)") (class "Default")
      (node (ref "R54") (pin "2") (pinfunction "2_2") (pintype "passive"))
      (node (ref "R55") (pin "1") (pinfunction "1_1") (pintype "passive"))
      (node (ref "TR10") (pin "3") (pinfunction "E_3") (pintype "passive"))
    )
    (net (code "63") (name "Net-(TR11-B)") (class "Default")
      (node (ref "C41") (pin "1") (pinfunction "1_1") (pintype "passive"))
      (node (ref "C49") (pin "2") (pinfunction "2_2") (pintype "passive"))
      (node (ref "R80") (pin "1") (pinfunction "1_1") (pintype "passive"))
      (node (ref "R89") (pin "2") (pinfunction "2_2") (pintype "passive"))
      (node (ref "TR11") (pin "1") (pinfunction "B_1") (pintype "passive"))
    )
    (net (code "64") (name "Net-(TR11-C)") (class "Default")
      (node (ref "C48") (pin "2") (pinfunction "2_2") (pintype "passive"))
      (node (ref "R68") (pin "1") (pinfunction "1_1") (pintype "passive"))
      (node (ref "R69") (pin "2") (pinfunction "2_2") (pintype "passive"))
      (node (ref "R73") (pin "1") (pinfunction "1_1") (pintype "passive"))
      (node (ref "TR11") (pin "2") (pinfunction "C_2") (pintype "passive"))
    )
    (net (code "65") (name "Net-(TR12-B)") (class "Default")
      (node (ref "C42") (pin "1") (pinfunction "1_1") (pintype "passive"))
      (node (ref "C48") (pin "1") (pinfunction "1_1") (pintype "passive"))
      (node (ref "R73") (pin "2") (pinfunction "2_2") (pintype "passive"))
      (node (ref "R74") (pin "2") (pinfunction "2_2") (pintype "passive"))
      (node (ref "TR12") (pin "1") (pinfunction "B_1") (pintype "passive"))
    )
    (net (code "66") (name "Net-(TR12-C)") (class "Default")
      (node (ref "C49") (pin "1") (pinfunction "1_1") (pintype "passive"))
      (node (ref "R70") (pin "1") (pinfunction "1_1") (pintype "passive"))
      (node (ref "R80") (pin "2") (pinfunction "2_2") (pintype "passive"))
      (node (ref "R88") (pin "1") (pinfunction "1_1") (pintype "passive"))
      (node (ref "TR12") (pin "2") (pinfunction "C_2") (pintype "passive"))
    )
    (net (code "67") (name "Net-(U1A-+IN)") (class "Default")
      (node (ref "R14") (pin "2") (pinfunction "2_2") (pintype "passive"))
      (node (ref "U1") (pin "3") (pinfunction "+IN_3") (pintype "input"))
    )
    (net (code "68") (name "Net-(U1A--IN)") (class "Default")
      (node (ref "C8") (pin "2") (pinfunction "2_2") (pintype "passive"))
      (node (ref "C9") (pin "+") (pinfunction "+_+") (pintype "passive"))
      (node (ref "R15") (pin "1") (pinfunction "1_1") (pintype "passive"))
      (node (ref "U1") (pin "2") (pinfunction "-IN_2") (pintype "input"))
    )
    (net (code "69") (name "Net-(U1A-OUT)") (class "Default")
      (node (ref "C11") (pin "2") (pinfunction "2_2") (pintype "passive"))
      (node (ref "C8") (pin "1") (pinfunction "1_1") (pintype "passive"))
      (node (ref "R15") (pin "2") (pinfunction "2_2") (pintype "passive"))
      (node (ref "U1") (pin "1") (pinfunction "OUT_1") (pintype "output"))
    )
    (net (code "70") (name "Net-(U1B-+IN)") (class "Default")
      (node (ref "R25") (pin "2") (pinfunction "2_2") (pintype "passive"))
      (node (ref "R67") (pin "2") (pinfunction "2_2") (pintype "passive"))
      (node (ref "U1") (pin "5") (pinfunction "+IN_5") (pintype "input"))
    )
    (net (code "71") (name "Net-(U1B--IN)") (class "Default")
      (node (ref "C18") (pin "2") (pinfunction "2_2") (pintype "passive"))
      (node (ref "R27") (pin "1") (pinfunction "1_1") (pintype "passive"))
      (node (ref "R91") (pin "2") (pinfunction "2_2") (pintype "passive"))
      (node (ref "U1") (pin "6") (pinfunction "-IN_6") (pintype "input"))
    )
    (net (code "72") (name "Net-(U1B-OUT)") (class "Default")
      (node (ref "C18") (pin "1") (pinfunction "1_1") (pintype "passive"))
      (node (ref "R29") (pin "1") (pinfunction "1_1") (pintype "passive"))
      (node (ref "U1") (pin "7") (pinfunction "OUT_7") (pintype "output"))
      (node (ref "VR1") (pin "2") (pinfunction "2_2") (pintype "passive"))
      (node (ref "VR1") (pin "3") (pinfunction "3_3") (pintype "passive"))
    )
    (net (code "73") (name "OUT") (class "Default")
      (node (ref "C36") (pin "-") (pinfunction "-_-") (pintype "passive"))
      (node (ref "R58") (pin "2") (pinfunction "2_2") (pintype "passive"))
    )
    (net (code "74") (name "VB") (class "Default")
      (node (ref "C38") (pin "+") (pinfunction "+_+") (pintype "passive"))
      (node (ref "R18") (pin "1") (pinfunction "1_1") (pintype "passive"))
      (node (ref "R22") (pin "1") (pinfunction "1_1") (pintype "passive"))
      (node (ref "R24") (pin "1") (pinfunction "1_1") (pintype "passive"))
      (node (ref "R31") (pin "1") (pinfunction "1_1") (pintype "passive"))
      (node (ref "R36") (pin "1") (pinfunction "1_1") (pintype "passive"))
      (node (ref "R39") (pin "1") (pinfunction "1_1") (pintype "passive"))
      (node (ref "R42") (pin "1") (pinfunction "1_1") (pintype "passive"))
      (node (ref "R45") (pin "1") (pinfunction "1_1") (pintype "passive"))
      (node (ref "R53") (pin "1") (pinfunction "1_1") (pintype "passive"))
      (node (ref "R59") (pin "2") (pinfunction "2_2") (pintype "passive"))
      (node (ref "R6") (pin "1") (pinfunction "1_1") (pintype "passive"))
      (node (ref "R60") (pin "2") (pinfunction "2_2") (pintype "passive"))
      (node (ref "R65") (pin "1") (pinfunction "1_1") (pintype "passive"))
      (node (ref "R75") (pin "1") (pinfunction "1_1") (pintype "passive"))
      (node (ref "SW1") (pin "P$4") (pinfunction "3_P$4") (pintype "bidirectional"))
      (node (ref "VR4") (pin "3") (pinfunction "3_3") (pintype "passive"))
    )
    (net (code "75") (name "unconnected-(R11-Pad2)") (class "Default")
      (node (ref "R11") (pin "2") (pinfunction "2_2") (pintype "passive"))
    )
  )
)
